# 03_-_Power_Supply.net
KiCad netlist of a schematic drawn in Altium Designer
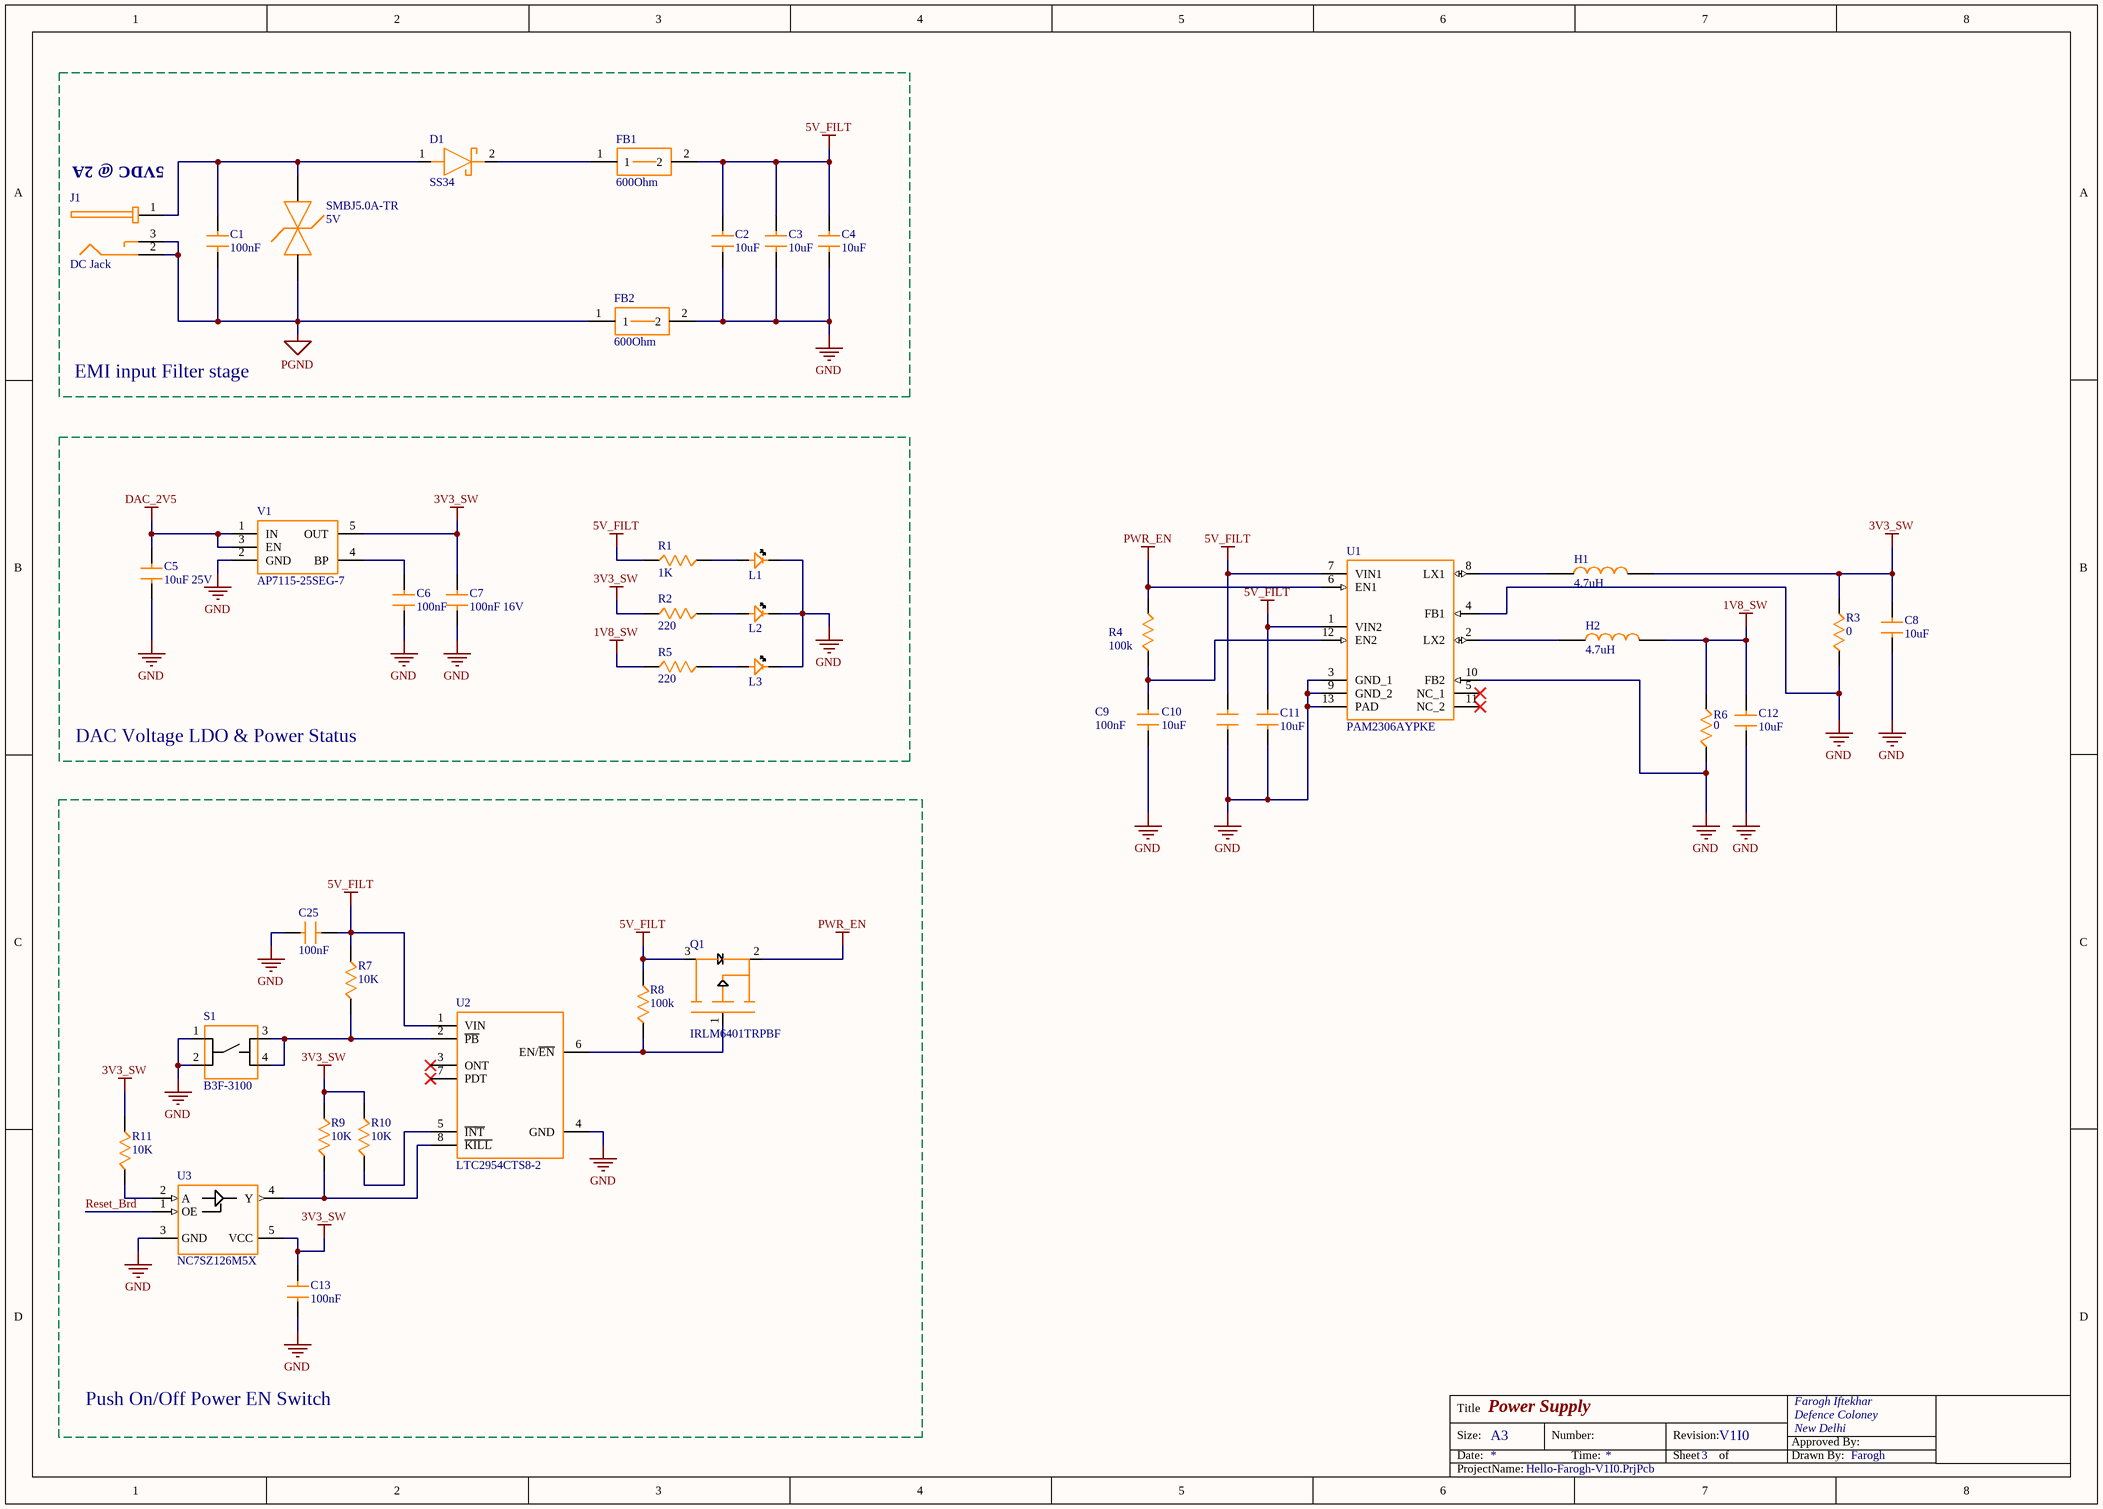
[diagram p0: [03] - Power Supply.SchDoc]

(export (version "E")
  (design (tool "Eeschema 10.0.6"))
  (components
    (comp (ref "C1")
      (value "100nF")
      (footprint "C0805")
      (description "Multilayer Ceramic Capacitors MLCC - SMD/SMT 100nF 16V 20% Ceramic Capacitor")
      (fields
        (field (name "MANUFACTURER") "Yageo")
        (field (name "MANUFACTURER PART NUMBER") "CC0805MRX7R7BB104")
      )
      (libsource (lib "Joule_Library") (part "C_0805-100nF-16V"))
    )
    (comp (ref "C2")
      (value "10uF")
      (footprint "C1206")
      (description "Multilayer Ceramic Capacitors MLCC - SMD/SMT 10uF Y5V -20/+80% 50V")
      (fields
        (field (name "MANUFACTURER") "Yageo")
        (field (name "MANUFACTURER PART NUMBER") "CC1210ZKY5V9BB106")
      )
      (libsource (lib "Joule_Library") (part "C_1206-10uF"))
    )
    (comp (ref "C3")
      (value "10uF")
      (footprint "C1206")
      (description "Multilayer Ceramic Capacitors MLCC - SMD/SMT 10uF Y5V -20/+80% 50V")
      (fields
        (field (name "MANUFACTURER") "Yageo")
        (field (name "MANUFACTURER PART NUMBER") "CC1210ZKY5V9BB106")
      )
      (libsource (lib "Joule_Library") (part "C_1206-10uF"))
    )
    (comp (ref "C4")
      (value "10uF")
      (footprint "C1206")
      (description "Multilayer Ceramic Capacitors MLCC - SMD/SMT 10uF Y5V -20/+80% 50V")
      (fields
        (field (name "MANUFACTURER") "Yageo")
        (field (name "MANUFACTURER PART NUMBER") "CC1210ZKY5V9BB106")
      )
      (libsource (lib "Joule_Library") (part "C_1206-10uF"))
    )
    (comp (ref "C5")
      (value "10uF 25V")
      (footprint "C0805")
      (description "Multilayer Ceramic Capacitors MLCC - SMD/SMT 10uF 10% 25V")
      (fields
        (field (name "MANUFACTURER") "Yageo")
        (field (name "MANUFACTURER PART NUMBER") "CC0805KFX5R8BB106")
      )
      (libsource (lib "Joule_Library") (part "C_0805-10uF"))
    )
    (comp (ref "C6")
      (value "100nF")
      (footprint "C0805")
      (description "Multilayer Ceramic Capacitors MLCC - SMD/SMT 100nF 16V 20% Ceramic Capacitor")
      (fields
        (field (name "MANUFACTURER") "Yageo")
        (field (name "MANUFACTURER PART NUMBER") "CC0805MRX7R7BB104")
      )
      (libsource (lib "Joule_Library") (part "C_0805-100nF-16V"))
    )
    (comp (ref "C7")
      (value "100nF 16V")
      (footprint "C0805")
      (description "Multilayer Ceramic Capacitors MLCC - SMD/SMT 100nF 16V 20% Ceramic Capacitor")
      (fields
        (field (name "MANUFACTURER") "Yageo")
        (field (name "MANUFACTURER PART NUMBER") "CC0805MRX7R7BB104")
      )
      (libsource (lib "Joule_Library") (part "C_0805-100nF-16V"))
    )
    (comp (ref "C8")
      (value "10uF")
      (footprint "C0805")
      (description "Multilayer Ceramic Capacitors MLCC - SMD/SMT 10uF 10% 25V")
      (fields
        (field (name "MANUFACTURER") "Yageo")
        (field (name "MANUFACTURER PART NUMBER") "CC0805KFX5R8BB106")
      )
      (libsource (lib "Joule_Library") (part "C_0805-10uF"))
    )
    (comp (ref "C9")
      (value "100nF")
      (footprint "C0805")
      (description "Multilayer Ceramic Capacitors MLCC - SMD/SMT 100nF 16V 20% Ceramic Capacitor")
      (fields
        (field (name "MANUFACTURER") "Yageo")
        (field (name "MANUFACTURER PART NUMBER") "CC0805MRX7R7BB104")
      )
      (libsource (lib "Joule_Library") (part "C_0805-100nF-16V"))
    )
    (comp (ref "C10")
      (value "10uF")
      (footprint "C0805")
      (description "Multilayer Ceramic Capacitors MLCC - SMD/SMT 10uF 10% 25V")
      (fields
        (field (name "MANUFACTURER") "Yageo")
        (field (name "MANUFACTURER PART NUMBER") "CC0805KFX5R8BB106")
      )
      (libsource (lib "Joule_Library") (part "C_0805-10uF"))
    )
    (comp (ref "C11")
      (value "10uF")
      (footprint "C0805")
      (description "Multilayer Ceramic Capacitors MLCC - SMD/SMT 10uF 10% 25V")
      (fields
        (field (name "MANUFACTURER") "Yageo")
        (field (name "MANUFACTURER PART NUMBER") "CC0805KFX5R8BB106")
      )
      (libsource (lib "Joule_Library") (part "C_0805-10uF"))
    )
    (comp (ref "C12")
      (value "10uF")
      (footprint "C0805")
      (description "Multilayer Ceramic Capacitors MLCC - SMD/SMT 10uF 10% 25V")
      (fields
        (field (name "MANUFACTURER") "Yageo")
        (field (name "MANUFACTURER PART NUMBER") "CC0805KFX5R8BB106")
      )
      (libsource (lib "Joule_Library") (part "C_0805-10uF"))
    )
    (comp (ref "C13")
      (value "100nF")
      (footprint "C0805")
      (description "Multilayer Ceramic Capacitors MLCC - SMD/SMT 100nF 16V 20% Ceramic Capacitor")
      (fields
        (field (name "MANUFACTURER") "Yageo")
        (field (name "MANUFACTURER PART NUMBER") "CC0805MRX7R7BB104")
      )
      (libsource (lib "Capacitor_0805") (part "C_0805-100nF-16V"))
    )
    (comp (ref "C25")
      (value "100nF")
      (footprint "C0805")
      (description "Multilayer Ceramic Capacitors MLCC - SMD/SMT 100nF 16V 20% Ceramic Capacitor")
      (fields
        (field (name "MANUFACTURER") "Yageo")
        (field (name "MANUFACTURER PART NUMBER") "CC0805MRX7R7BB104")
      )
      (libsource (lib "Capacitor_0805") (part "C_0805-100nF-16V"))
    )
    (comp (ref "D1")
      (value "SS34")
      (footprint "SS34")
      (description "Schottky Diodes & Rectifiers 3a 40V Rectifier Schottky Barrier")
      (fields (field (name "MANUFACTURER") "ON Semiconductor / Fairchild"))
      (libsource (lib "Joule_Library") (part "SS34"))
    )
    (comp (ref "FB1")
      (value "600Ohm")
      (footprint "FB_1210")
      (description "Ferrite Beads HI CUR CHIP BD 1210 600OHMS 30%")
      (fields
        (field (name "MANUFACTURER") "Taiyo Yuden")
        (field (name "MANUFACTURER PART NUMBER") "FBMH3225HM601NT")
      )
      (libsource (lib "Joule_Library") (part "FB_1210-600, 3000mA"))
    )
    (comp (ref "FB2")
      (value "600Ohm")
      (footprint "FB_1210")
      (description "Ferrite Beads HI CUR CHIP BD 1210 600OHMS 30%")
      (fields
        (field (name "MANUFACTURER") "Taiyo Yuden")
        (field (name "MANUFACTURER PART NUMBER") "FBMH3225HM601NT")
      )
      (libsource (lib "Joule_Library") (part "FB_1210-600, 3000mA"))
    )
    (comp (ref "H1")
      (value "4.7uH")
      (footprint "SRN4018")
      (description "Fixed Inductors 4.7uH 20% SMD 4018")
      (fields (field (name "MANUFACTURER") "Bourns") (field (name "MANUFACTURER PART NUMBER") "SRN4018-4R7M"))
      (libsource (lib "Joule_Library") (part "SRN4018-4R7M"))
    )
    (comp (ref "H2")
      (value "4.7uH")
      (footprint "SRN4018")
      (description "Fixed Inductors 4.7uH 20% SMD 4018")
      (fields (field (name "MANUFACTURER") "Bourns") (field (name "MANUFACTURER PART NUMBER") "SRN4018-4R7M"))
      (libsource (lib "Joule_Library") (part "SRN4018-4R7M"))
    )
    (comp (ref "J1")
      (value "DC Jack")
      (footprint "PJ-059BH")
      (description "DC Power Connectors power jack, 2.5 x 5.5 mm, horizontal, through hole, high current, 1 switch")
      (fields (field (name "MANUFACTURER") "CUI") (field (name "MANUFACTURER PART NUMBER") "PJ-059BH"))
      (libsource (lib "Joule_Library") (part "DC-PJ-059BH"))
    )
    (comp (ref "L1")
      (value "599-0130-007F")
      (footprint "LED0805")
      (description "Standard LEDs - SMD SMD 0805 ORANGE")
      (fields (field (name "MANUFACTURER") "Dialight"))
      (libsource (lib "Joule_Library") (part "599-0130-007F"))
    )
    (comp (ref "L2")
      (value "599-0130-007F")
      (footprint "LED0805")
      (description "Standard LEDs - SMD SMD 0805 ORANGE")
      (fields (field (name "MANUFACTURER") "Dialight"))
      (libsource (lib "Joule_Library") (part "599-0130-007F"))
    )
    (comp (ref "L3")
      (value "599-0130-007F")
      (footprint "LED0805")
      (description "Standard LEDs - SMD SMD 0805 ORANGE")
      (fields (field (name "MANUFACTURER") "Dialight"))
      (libsource (lib "Joule_Library") (part "599-0130-007F"))
    )
    (comp (ref "Q1")
      (value "IRLM6401TRPBF")
      (footprint "IRLML6401TRPBF")
      (description "MOSFET MOSFT P-Ch -4.3A 50mOhm 10nC Log Lvl")
      (fields
        (field (name "MANUFACTURER") "Infineon Technologies")
        (field (name "MANUFACTURER PART NUMBER") "IRLML6401TRPBF")
      )
      (libsource (lib "Joule_Library") (part "IRLML6401TRPBF"))
    )
    (comp (ref "R1")
      (value "1K")
      (footprint "R0805")
      (description "Thin Film Resistors - SMD 1K ohm 1% 50 ppm Thin Film")
      (fields
        (field (name "MANUFACTURER") "Yageo")
        (field (name "MANUFACTURER PART NUMBER") "RT0805FRE101KL")
      )
      (libsource (lib "Joule_Library") (part "R_0805-1K"))
    )
    (comp (ref "R2")
      (value "220")
      (footprint "R0805")
      (description "Thin Film Resistors - SMD")
      (fields
        (field (name "MANUFACTURER") "Yageo")
        (field (name "MANUFACTURER PART NUMBER") "RT0805DRE07220RL")
      )
      (libsource (lib "Joule_Library") (part "R_0805-220"))
    )
    (comp (ref "R3")
      (value "0")
      (footprint "R0805")
      (description "Current Sense Resistors - SMD 0 ohm Jumper 1/2W")
      (fields
        (field (name "MANUFACTURER") "Yageo")
        (field (name "MANUFACTURER PART NUMBER") "PA0805-R-470RL")
      )
      (libsource (lib "Joule_Library") (part "R_0805-0"))
    )
    (comp (ref "R4")
      (value "100k")
      (footprint "R0805")
      (description "Thick Film Resistors - SMD 100K ohm 1% 150V AEC-Q200")
      (fields
        (field (name "MANUFACTURER") "Yageo")
        (field (name "MANUFACTURER PART NUMBER") "AC0805FR-13100KL")
      )
      (libsource (lib "Joule_Library") (part "R_0805-100K"))
    )
    (comp (ref "R5")
      (value "220")
      (footprint "R0805")
      (description "Thin Film Resistors - SMD")
      (fields
        (field (name "MANUFACTURER") "Yageo")
        (field (name "MANUFACTURER PART NUMBER") "RT0805DRE07220RL")
      )
      (libsource (lib "Joule_Library") (part "R_0805-220"))
    )
    (comp (ref "R6")
      (value "0")
      (footprint "R0805")
      (description "Current Sense Resistors - SMD 0 ohm Jumper 1/2W")
      (fields
        (field (name "MANUFACTURER") "Yageo")
        (field (name "MANUFACTURER PART NUMBER") "PA0805-R-470RL")
      )
      (libsource (lib "Joule_Library") (part "R_0805-0"))
    )
    (comp (ref "R7")
      (value "10K")
      (footprint "R0805")
      (description "Thick Film Resistors - SMD 10K   OHM   1% 1/4W")
      (fields
        (field (name "MANUFACTURER") "Yageo")
        (field (name "MANUFACTURER PART NUMBER") "RC0805FR-7W10KL")
      )
      (libsource (lib "Joule_Library") (part "R_0805-10K"))
    )
    (comp (ref "R8")
      (value "100k")
      (footprint "R0805")
      (description "Thick Film Resistors - SMD 100K ohm 1% 150V AEC-Q200")
      (fields
        (field (name "MANUFACTURER") "Yageo")
        (field (name "MANUFACTURER PART NUMBER") "AC0805FR-13100KL")
      )
      (libsource (lib "Joule_Library") (part "R_0805-100K"))
    )
    (comp (ref "R9")
      (value "10K")
      (footprint "R0805")
      (description "Thick Film Resistors - SMD 10K   OHM   1% 1/4W")
      (fields
        (field (name "MANUFACTURER") "Yageo")
        (field (name "MANUFACTURER PART NUMBER") "RC0805FR-7W10KL")
      )
      (libsource (lib "Joule_Library") (part "R_0805-10K"))
    )
    (comp (ref "R10")
      (value "10K")
      (footprint "R0805")
      (description "Thick Film Resistors - SMD 10K   OHM   1% 1/4W")
      (fields
        (field (name "MANUFACTURER") "Yageo")
        (field (name "MANUFACTURER PART NUMBER") "RC0805FR-7W10KL")
      )
      (libsource (lib "Joule_Library") (part "R_0805-10K"))
    )
    (comp (ref "R11")
      (value "10K")
      (footprint "R0805")
      (description "Thick Film Resistors - SMD 10K   OHM   1% 1/4W")
      (fields
        (field (name "MANUFACTURER") "Yageo")
        (field (name "MANUFACTURER PART NUMBER") "RC0805FR-7W10KL")
      )
      (libsource (lib "Joule_Library") (part "R_0805-10K"))
    )
    (comp (ref "S1")
      (value "B3F-3100")
      (footprint "BSF-3100")
      (description "Tactile Switches 3.15mm VERT 100gF")
      (fields (field (name "MANUFACTURER") "Omron Electronics"))
      (libsource (lib "Joule_Library") (part "B3F-3100"))
    )
    (comp (ref "SMBJ5.0A-TR")
      (value "5V")
      (footprint "SMBJ5.0A-TR")
      (description "ESD Suppressors / TVS Diodes 600W 5.0V Unidirect")
      (fields
        (field (name "MANUFACTURER") "STMicroelectronics")
        (field (name "MANUFACTURER PART NUMBER") "SMBJ5.0A-TR")
      )
      (libsource (lib "Joule_Library") (part "SMBJ5.0A-TR"))
    )
    (comp (ref "U1")
      (value "PAM2306AYPKE")
      (footprint "PAM2306AYPKE")
      (description "Switching Voltage Regulators Dual PWM Step-Down 40uA 1A 1.5MHz")
      (fields (field (name "MANUFACTURER") "Diodes Incorporated"))
      (libsource (lib "ICs") (part "PAM2306AYPKE"))
    )
    (comp (ref "U2")
      (value "LTC2954CTS8-2")
      (footprint "LTC2954CTS8-2")
      (description "Supervisory Circuits Push Button On/Off Controller with U Interrupt for Menu Driven Applications")
      (fields
        (field (name "MANUFACTURER") "Analog Devices")
        (field (name "MANUFACTURER PART NUMBER") "LTC2954CTS8-2#TRMPBF")
      )
      (libsource (lib "Joule_Library") (part "LTC2954CTS8-2"))
    )
    (comp (ref "U3")
      (value "NC7SZ126M5X")
      (footprint "NC7SZ126M5X")
      (description "Buffers & Line Drivers UHS Buffer")
      (fields (field (name "MANUFACTURER") "ON Semiconductor / Fairchild"))
      (libsource (lib "Joule_Library") (part "NC7SZ126M5X"))
    )
    (comp (ref "V1")
      (value "AP7115-25SEG-7")
      (footprint "AP7115-25SEG-7")
      (description "LDO Voltage Regulators LDO SNGLE OUTPUT 150MA 220MV 2.5-5.5V")
      (fields (field (name "MANUFACTURER") "Diodes Incorporated"))
      (libsource (lib "Regulator") (part "AP7115-25SEG-7"))
    )
  )
  (nets
    (net (code "1") (name "/Reset_Brd") (class "Default")
      (node (ref "U3") (pin "1") (pinfunction "OE_1") (pintype "input"))
    )
    (net (code "2") (name "1V8_SW") (class "Default")
      (node (ref "C12") (pin "2") (pinfunction "2_2") (pintype "passive"))
      (node (ref "H2") (pin "2") (pinfunction "2_2") (pintype "passive"))
      (node (ref "R5") (pin "1") (pinfunction "1_1") (pintype "passive"))
      (node (ref "R6") (pin "2") (pinfunction "2_2") (pintype "passive"))
    )
    (net (code "3") (name "3V3_SW") (class "Default")
      (node (ref "C13") (pin "1") (pinfunction "1_1") (pintype "passive"))
      (node (ref "C7") (pin "2") (pinfunction "2_2") (pintype "passive"))
      (node (ref "C8") (pin "2") (pinfunction "2_2") (pintype "passive"))
      (node (ref "H1") (pin "2") (pinfunction "2_2") (pintype "passive"))
      (node (ref "R10") (pin "2") (pinfunction "2_2") (pintype "passive"))
      (node (ref "R11") (pin "1") (pinfunction "1_1") (pintype "passive"))
      (node (ref "R2") (pin "1") (pinfunction "1_1") (pintype "passive"))
      (node (ref "R3") (pin "2") (pinfunction "2_2") (pintype "passive"))
      (node (ref "R9") (pin "1") (pinfunction "1_1") (pintype "passive"))
      (node (ref "U3") (pin "5") (pinfunction "VCC_5") (pintype "power_in"))
      (node (ref "V1") (pin "5") (pinfunction "OUT_5") (pintype "passive"))
    )
    (net (code "4") (name "5V_FILT") (class "Default")
      (node (ref "C10") (pin "2") (pinfunction "2_2") (pintype "passive"))
      (node (ref "C11") (pin "2") (pinfunction "2_2") (pintype "passive"))
      (node (ref "C2") (pin "2") (pinfunction "2_2") (pintype "passive"))
      (node (ref "C25") (pin "1") (pinfunction "1_1") (pintype "passive"))
      (node (ref "C3") (pin "2") (pinfunction "2_2") (pintype "passive"))
      (node (ref "C4") (pin "2") (pinfunction "2_2") (pintype "passive"))
      (node (ref "FB1") (pin "2") (pinfunction "2_2") (pintype "passive"))
      (node (ref "Q1") (pin "3") (pinfunction "D_3") (pintype "passive"))
      (node (ref "R1") (pin "1") (pinfunction "1_1") (pintype "passive"))
      (node (ref "R7") (pin "2") (pinfunction "2_2") (pintype "passive"))
      (node (ref "R8") (pin "2") (pinfunction "2_2") (pintype "passive"))
      (node (ref "U1") (pin "1") (pinfunction "VIN2_1") (pintype "power_in"))
      (node (ref "U1") (pin "7") (pinfunction "VIN1_7") (pintype "power_in"))
      (node (ref "U2") (pin "1") (pinfunction "VIN_1") (pintype "passive"))
    )
    (net (code "5") (name "DAC_2V5") (class "Default")
      (node (ref "C5") (pin "2") (pinfunction "2_2") (pintype "passive"))
      (node (ref "V1") (pin "1") (pinfunction "IN_1") (pintype "passive"))
      (node (ref "V1") (pin "3") (pinfunction "EN_3") (pintype "passive"))
    )
    (net (code "6") (name "GND") (class "Default")
      (node (ref "C10") (pin "1") (pinfunction "1_1") (pintype "passive"))
      (node (ref "C11") (pin "1") (pinfunction "1_1") (pintype "passive"))
      (node (ref "C12") (pin "1") (pinfunction "1_1") (pintype "passive"))
      (node (ref "C13") (pin "2") (pinfunction "2_2") (pintype "passive"))
      (node (ref "C2") (pin "1") (pinfunction "1_1") (pintype "passive"))
      (node (ref "C25") (pin "2") (pinfunction "2_2") (pintype "passive"))
      (node (ref "C3") (pin "1") (pinfunction "1_1") (pintype "passive"))
      (node (ref "C4") (pin "1") (pinfunction "1_1") (pintype "passive"))
      (node (ref "C5") (pin "1") (pinfunction "1_1") (pintype "passive"))
      (node (ref "C6") (pin "1") (pinfunction "1_1") (pintype "passive"))
      (node (ref "C7") (pin "1") (pinfunction "1_1") (pintype "passive"))
      (node (ref "C8") (pin "1") (pinfunction "1_1") (pintype "passive"))
      (node (ref "C9") (pin "1") (pinfunction "1_1") (pintype "passive"))
      (node (ref "FB2") (pin "2") (pinfunction "2_2") (pintype "passive"))
      (node (ref "L1") (pin "2") (pinfunction "2_2") (pintype "passive"))
      (node (ref "L2") (pin "2") (pinfunction "2_2") (pintype "passive"))
      (node (ref "L3") (pin "2") (pinfunction "2_2") (pintype "passive"))
      (node (ref "R3") (pin "1") (pinfunction "1_1") (pintype "passive"))
      (node (ref "R6") (pin "1") (pinfunction "1_1") (pintype "passive"))
      (node (ref "S1") (pin "1") (pinfunction "1_1") (pintype "passive"))
      (node (ref "S1") (pin "2") (pinfunction "2_2") (pintype "passive"))
      (node (ref "U1") (pin "10") (pinfunction "FB2_10") (pintype "input"))
      (node (ref "U1") (pin "13") (pinfunction "PAD_13") (pintype "power_in"))
      (node (ref "U1") (pin "3") (pinfunction "GND_1_3") (pintype "power_in"))
      (node (ref "U1") (pin "4") (pinfunction "FB1_4") (pintype "input"))
      (node (ref "U1") (pin "9") (pinfunction "GND_2_9") (pintype "power_in"))
      (node (ref "U2") (pin "4") (pinfunction "GND_4") (pintype "passive"))
      (node (ref "U3") (pin "3") (pinfunction "GND_3") (pintype "power_in"))
      (node (ref "V1") (pin "2") (pinfunction "GND_2") (pintype "passive"))
    )
    (net (code "7") (name "Net-(D1-A)") (class "Default")
      (node (ref "C1") (pin "2") (pinfunction "2_2") (pintype "passive"))
      (node (ref "D1") (pin "1") (pinfunction "A_1") (pintype "passive"))
      (node (ref "J1") (pin "1") (pinfunction "1_1") (pintype "passive"))
      (node (ref "SMBJ5.0A-TR") (pin "1") (pinfunction "K_1") (pintype "passive"))
    )
    (net (code "8") (name "Net-(D1-K)") (class "Default")
      (node (ref "D1") (pin "2") (pinfunction "K_2") (pintype "passive"))
      (node (ref "FB1") (pin "1") (pinfunction "1_1") (pintype "passive"))
    )
    (net (code "9") (name "Net-(L1-Pad1)") (class "Default")
      (node (ref "L1") (pin "1") (pinfunction "1_1") (pintype "passive"))
      (node (ref "R1") (pin "2") (pinfunction "2_2") (pintype "passive"))
    )
    (net (code "10") (name "Net-(L2-Pad1)") (class "Default")
      (node (ref "L2") (pin "1") (pinfunction "1_1") (pintype "passive"))
      (node (ref "R2") (pin "2") (pinfunction "2_2") (pintype "passive"))
    )
    (net (code "11") (name "Net-(L3-Pad1)") (class "Default")
      (node (ref "L3") (pin "1") (pinfunction "1_1") (pintype "passive"))
      (node (ref "R5") (pin "2") (pinfunction "2_2") (pintype "passive"))
    )
    (net (code "12") (name "Net-(Q1-G)") (class "Default")
      (node (ref "Q1") (pin "1") (pinfunction "G_1") (pintype "passive"))
      (node (ref "R8") (pin "1") (pinfunction "1_1") (pintype "passive"))
      (node (ref "U2") (pin "6") (pinfunction "EN/~{EN}_6") (pintype "passive"))
    )
    (net (code "13") (name "Net-(U1-EN2)") (class "Default")
      (node (ref "C9") (pin "2") (pinfunction "2_2") (pintype "passive"))
      (node (ref "R4") (pin "1") (pinfunction "1_1") (pintype "passive"))
      (node (ref "U1") (pin "12") (pinfunction "EN2_12") (pintype "input"))
    )
    (net (code "14") (name "Net-(U1-LX1)") (class "Default")
      (node (ref "H1") (pin "1") (pinfunction "1_1") (pintype "passive"))
      (node (ref "U1") (pin "8") (pinfunction "LX1_8") (pintype "bidirectional"))
    )
    (net (code "15") (name "Net-(U1-LX2)") (class "Default")
      (node (ref "H2") (pin "1") (pinfunction "1_1") (pintype "passive"))
      (node (ref "U1") (pin "2") (pinfunction "LX2_2") (pintype "bidirectional"))
    )
    (net (code "16") (name "Net-(U2-~{INT})") (class "Default")
      (node (ref "R10") (pin "1") (pinfunction "1_1") (pintype "passive"))
      (node (ref "U2") (pin "5") (pinfunction "~{INT}_5") (pintype "passive"))
    )
    (net (code "17") (name "Net-(U2-~{KILL})") (class "Default")
      (node (ref "R9") (pin "2") (pinfunction "2_2") (pintype "passive"))
      (node (ref "U2") (pin "8") (pinfunction "~{KILL}_8") (pintype "passive"))
      (node (ref "U3") (pin "4") (pinfunction "Y_4") (pintype "output"))
    )
    (net (code "18") (name "Net-(U2-~{PB})") (class "Default")
      (node (ref "R7") (pin "1") (pinfunction "1_1") (pintype "passive"))
      (node (ref "S1") (pin "3") (pinfunction "3_3") (pintype "passive"))
      (node (ref "S1") (pin "4") (pinfunction "4_4") (pintype "passive"))
      (node (ref "U2") (pin "2") (pinfunction "~{PB}_2") (pintype "passive"))
    )
    (net (code "19") (name "Net-(U3-A)") (class "Default")
      (node (ref "R11") (pin "2") (pinfunction "2_2") (pintype "passive"))
      (node (ref "U3") (pin "2") (pinfunction "A_2") (pintype "input"))
    )
    (net (code "20") (name "Net-(V1-BP)") (class "Default")
      (node (ref "C6") (pin "2") (pinfunction "2_2") (pintype "passive"))
      (node (ref "V1") (pin "4") (pinfunction "BP_4") (pintype "passive"))
    )
    (net (code "21") (name "PGND") (class "Default")
      (node (ref "C1") (pin "1") (pinfunction "1_1") (pintype "passive"))
      (node (ref "FB2") (pin "1") (pinfunction "1_1") (pintype "passive"))
      (node (ref "J1") (pin "2") (pinfunction "2_2") (pintype "passive"))
      (node (ref "J1") (pin "3") (pinfunction "3_3") (pintype "passive"))
      (node (ref "SMBJ5.0A-TR") (pin "2") (pinfunction "A_2") (pintype "passive"))
    )
    (net (code "22") (name "PWR_EN") (class "Default")
      (node (ref "Q1") (pin "2") (pinfunction "S_2") (pintype "passive"))
      (node (ref "R4") (pin "2") (pinfunction "2_2") (pintype "passive"))
      (node (ref "U1") (pin "6") (pinfunction "EN1_6") (pintype "input"))
    )
    (net (code "23") (name "unconnected-(U1-NC_1-Pad5)") (class "Default")
      (node (ref "U1") (pin "5") (pinfunction "NC_1_5") (pintype "passive+no_connect"))
    )
    (net (code "24") (name "unconnected-(U1-NC_2-Pad11)") (class "Default")
      (node (ref "U1") (pin "11") (pinfunction "NC_2_11") (pintype "passive+no_connect"))
    )
    (net (code "25") (name "unconnected-(U2-ONT-Pad3)") (class "Default")
      (node (ref "U2") (pin "3") (pinfunction "ONT_3") (pintype "passive+no_connect"))
    )
    (net (code "26") (name "unconnected-(U2-PDT-Pad7)") (class "Default")
      (node (ref "U2") (pin "7") (pinfunction "PDT_7") (pintype "passive+no_connect"))
    )
  )
)
